# Atmega32_Breakout.net
KiCad netlist of a schematic drawn in EAGLE
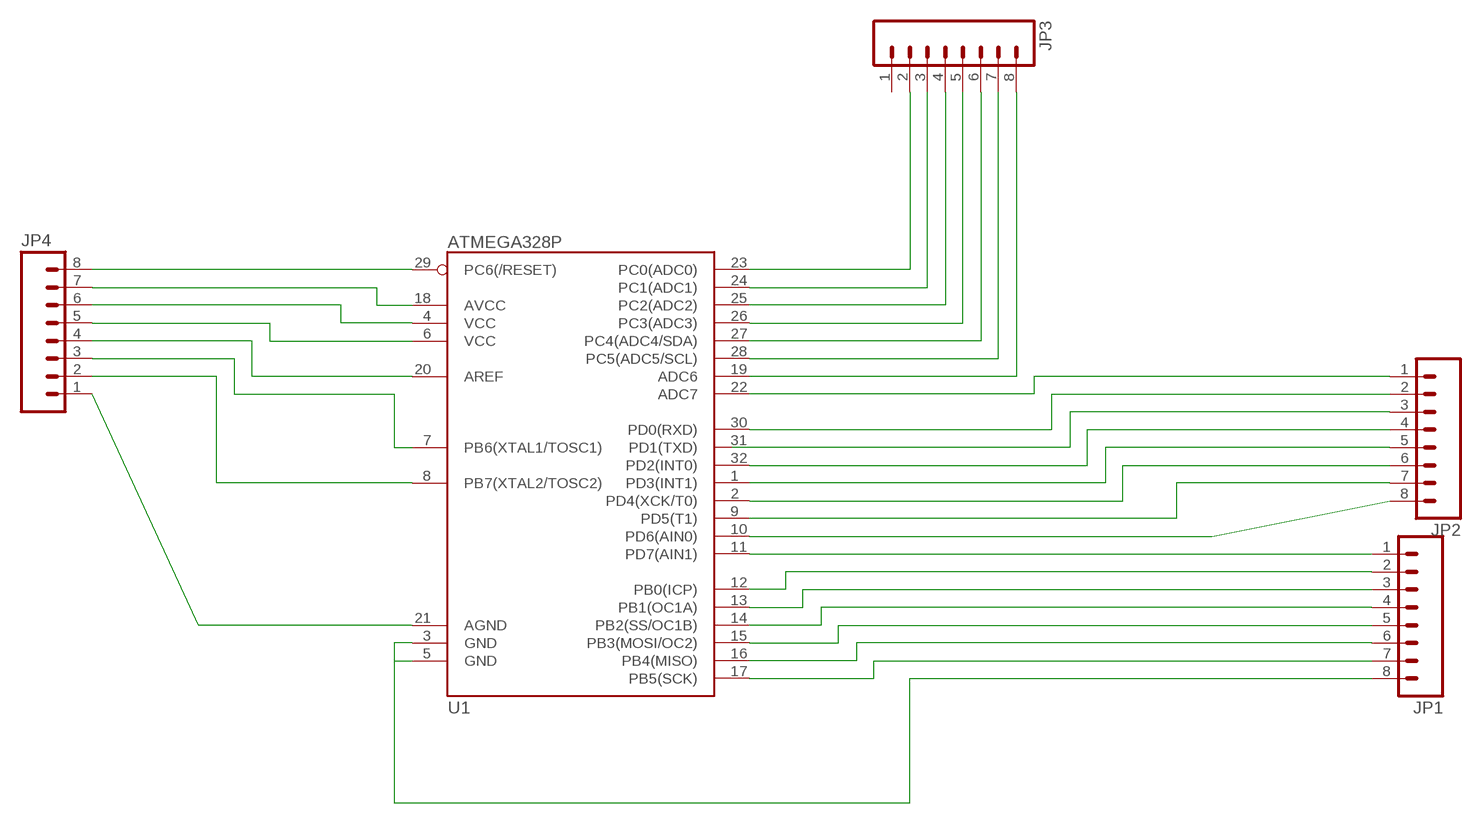
[diagram p0: schematic, sheet 1]

(export (version "E")
  (design (tool "Eeschema 10.0.6"))
  (components
    (comp (ref "JP1")
      (value "M08")
      (footprint "eagle-import:1X08_PIN1_NO_SILK")
      (libsource (lib "eagle-import") (part "M08"))
    )
    (comp (ref "JP2")
      (value "M08")
      (footprint "eagle-import:1X08_PIN1_NO_SILK")
      (libsource (lib "eagle-import") (part "M08"))
    )
    (comp (ref "JP3")
      (value "M08")
      (footprint "eagle-import:1X08_PIN1_NO_SILK")
      (libsource (lib "eagle-import") (part "M08"))
    )
    (comp (ref "JP4")
      (value "M08")
      (footprint "eagle-import:1X08_PIN1_NO_SILK")
      (libsource (lib "eagle-import") (part "M08"))
    )
    (comp (ref "U1")
      (value "ATMEGA328P")
      (footprint "eagle-import:TQFP32-08")
      (libsource (lib "eagle-import") (part "ATMEGA328_SMT"))
    )
  )
  (nets
    (net (code "1") (name "/VCC") (class "Default")
      (node (ref "JP4") (pin "5") (pinfunction "5_5") (pintype "passive"))
      (node (ref "JP4") (pin "6") (pinfunction "6_6") (pintype "passive"))
      (node (ref "U1") (pin "4") (pinfunction "VCC_4") (pintype "bidirectional"))
      (node (ref "U1") (pin "6") (pinfunction "VCC_6") (pintype "bidirectional"))
    )
    (net (code "2") (name "Net-(JP1-Pad8)") (class "Default")
      (node (ref "JP1") (pin "8") (pinfunction "8_8") (pintype "passive"))
      (node (ref "U1") (pin "3") (pinfunction "GND_3") (pintype "bidirectional"))
      (node (ref "U1") (pin "5") (pinfunction "GND_5") (pintype "bidirectional"))
    )
    (net (code "3") (name "Net-(U1-ADC6)") (class "Default")
      (node (ref "JP3") (pin "8") (pinfunction "8_8") (pintype "passive"))
      (node (ref "U1") (pin "19") (pinfunction "ADC6_19") (pintype "bidirectional"))
    )
    (net (code "4") (name "Net-(U1-ADC7)") (class "Default")
      (node (ref "JP2") (pin "1") (pinfunction "1_1") (pintype "passive"))
      (node (ref "U1") (pin "22") (pinfunction "ADC7_22") (pintype "bidirectional"))
    )
    (net (code "5") (name "Net-(U1-AGND)") (class "Default")
      (node (ref "JP4") (pin "1") (pinfunction "1_1") (pintype "passive"))
      (node (ref "U1") (pin "21") (pinfunction "AGND_21") (pintype "bidirectional"))
    )
    (net (code "6") (name "Net-(U1-AREF)") (class "Default")
      (node (ref "JP4") (pin "4") (pinfunction "4_4") (pintype "passive"))
      (node (ref "U1") (pin "20") (pinfunction "AREF_20") (pintype "bidirectional"))
    )
    (net (code "7") (name "Net-(U1-AVCC)") (class "Default")
      (node (ref "JP4") (pin "7") (pinfunction "7_7") (pintype "passive"))
      (node (ref "U1") (pin "18") (pinfunction "AVCC_18") (pintype "bidirectional"))
    )
    (net (code "8") (name "Net-(U1-PB0(ICP))") (class "Default")
      (node (ref "JP1") (pin "2") (pinfunction "2_2") (pintype "passive"))
      (node (ref "U1") (pin "12") (pinfunction "PB0(ICP)_12") (pintype "bidirectional"))
    )
    (net (code "9") (name "Net-(U1-PB1(OC1A))") (class "Default")
      (node (ref "JP1") (pin "3") (pinfunction "3_3") (pintype "passive"))
      (node (ref "U1") (pin "13") (pinfunction "PB1(OC1A)_13") (pintype "bidirectional"))
    )
    (net (code "10") (name "Net-(U1-PB2(SS{slash}OC1B))") (class "Default")
      (node (ref "JP1") (pin "4") (pinfunction "4_4") (pintype "passive"))
      (node (ref "U1") (pin "14") (pinfunction "PB2(SS/OC1B)_14") (pintype "bidirectional"))
    )
    (net (code "11") (name "Net-(U1-PB3(MOSI{slash}OC2))") (class "Default")
      (node (ref "JP1") (pin "5") (pinfunction "5_5") (pintype "passive"))
      (node (ref "U1") (pin "15") (pinfunction "PB3(MOSI/OC2)_15") (pintype "bidirectional"))
    )
    (net (code "12") (name "Net-(U1-PB4(MISO))") (class "Default")
      (node (ref "JP1") (pin "6") (pinfunction "6_6") (pintype "passive"))
      (node (ref "U1") (pin "16") (pinfunction "PB4(MISO)_16") (pintype "bidirectional"))
    )
    (net (code "13") (name "Net-(U1-PB5(SCK))") (class "Default")
      (node (ref "JP1") (pin "7") (pinfunction "7_7") (pintype "passive"))
      (node (ref "U1") (pin "17") (pinfunction "PB5(SCK)_17") (pintype "bidirectional"))
    )
    (net (code "14") (name "Net-(U1-PB6(XTAL1{slash}TOSC1))") (class "Default")
      (node (ref "JP4") (pin "3") (pinfunction "3_3") (pintype "passive"))
      (node (ref "U1") (pin "7") (pinfunction "PB6(XTAL1/TOSC1)_7") (pintype "bidirectional"))
    )
    (net (code "15") (name "Net-(U1-PB7(XTAL2{slash}TOSC2))") (class "Default")
      (node (ref "JP4") (pin "2") (pinfunction "2_2") (pintype "passive"))
      (node (ref "U1") (pin "8") (pinfunction "PB7(XTAL2/TOSC2)_8") (pintype "bidirectional"))
    )
    (net (code "16") (name "Net-(U1-PC0(ADC0))") (class "Default")
      (node (ref "JP3") (pin "2") (pinfunction "2_2") (pintype "passive"))
      (node (ref "U1") (pin "23") (pinfunction "PC0(ADC0)_23") (pintype "bidirectional"))
    )
    (net (code "17") (name "Net-(U1-PC1(ADC1))") (class "Default")
      (node (ref "JP3") (pin "3") (pinfunction "3_3") (pintype "passive"))
      (node (ref "U1") (pin "24") (pinfunction "PC1(ADC1)_24") (pintype "bidirectional"))
    )
    (net (code "18") (name "Net-(U1-PC2(ADC2))") (class "Default")
      (node (ref "JP3") (pin "4") (pinfunction "4_4") (pintype "passive"))
      (node (ref "U1") (pin "25") (pinfunction "PC2(ADC2)_25") (pintype "bidirectional"))
    )
    (net (code "19") (name "Net-(U1-PC3(ADC3))") (class "Default")
      (node (ref "JP3") (pin "5") (pinfunction "5_5") (pintype "passive"))
      (node (ref "U1") (pin "26") (pinfunction "PC3(ADC3)_26") (pintype "bidirectional"))
    )
    (net (code "20") (name "Net-(U1-PC4(ADC4{slash}SDA))") (class "Default")
      (node (ref "JP3") (pin "6") (pinfunction "6_6") (pintype "passive"))
      (node (ref "U1") (pin "27") (pinfunction "PC4(ADC4/SDA)_27") (pintype "bidirectional"))
    )
    (net (code "21") (name "Net-(U1-PC5(ADC5{slash}SCL))") (class "Default")
      (node (ref "JP3") (pin "7") (pinfunction "7_7") (pintype "passive"))
      (node (ref "U1") (pin "28") (pinfunction "PC5(ADC5/SCL)_28") (pintype "bidirectional"))
    )
    (net (code "22") (name "Net-(U1-PC6({slash}RESET))") (class "Default")
      (node (ref "JP4") (pin "8") (pinfunction "8_8") (pintype "passive"))
      (node (ref "U1") (pin "29") (pinfunction "PC6(/RESET)_29") (pintype "bidirectional"))
    )
    (net (code "23") (name "Net-(U1-PD0(RXD))") (class "Default")
      (node (ref "JP2") (pin "2") (pinfunction "2_2") (pintype "passive"))
      (node (ref "U1") (pin "30") (pinfunction "PD0(RXD)_30") (pintype "bidirectional"))
    )
    (net (code "24") (name "Net-(U1-PD2(INT0))") (class "Default")
      (node (ref "JP2") (pin "4") (pinfunction "4_4") (pintype "passive"))
      (node (ref "U1") (pin "32") (pinfunction "PD2(INT0)_32") (pintype "bidirectional"))
    )
    (net (code "25") (name "Net-(U1-PD3(INT1))") (class "Default")
      (node (ref "JP2") (pin "5") (pinfunction "5_5") (pintype "passive"))
      (node (ref "U1") (pin "1") (pinfunction "PD3(INT1)_1") (pintype "bidirectional"))
    )
    (net (code "26") (name "Net-(U1-PD4(XCK{slash}T0))") (class "Default")
      (node (ref "JP2") (pin "6") (pinfunction "6_6") (pintype "passive"))
      (node (ref "U1") (pin "2") (pinfunction "PD4(XCK/T0)_2") (pintype "bidirectional"))
    )
    (net (code "27") (name "Net-(U1-PD5(T1))") (class "Default")
      (node (ref "JP2") (pin "7") (pinfunction "7_7") (pintype "passive"))
      (node (ref "U1") (pin "9") (pinfunction "PD5(T1)_9") (pintype "bidirectional"))
    )
    (net (code "28") (name "Net-(U1-PD6(AIN0))") (class "Default")
      (node (ref "JP2") (pin "8") (pinfunction "8_8") (pintype "passive"))
      (node (ref "U1") (pin "10") (pinfunction "PD6(AIN0)_10") (pintype "bidirectional"))
    )
    (net (code "29") (name "Net-(U1-PD7(AIN1))") (class "Default")
      (node (ref "JP1") (pin "1") (pinfunction "1_1") (pintype "passive"))
      (node (ref "U1") (pin "11") (pinfunction "PD7(AIN1)_11") (pintype "bidirectional"))
    )
    (net (code "30") (name "unconnected-(JP2-Pad3)") (class "Default")
      (node (ref "JP2") (pin "3") (pinfunction "3_3") (pintype "passive"))
    )
    (net (code "31") (name "unconnected-(JP3-Pad1)") (class "Default")
      (node (ref "JP3") (pin "1") (pinfunction "1_1") (pintype "passive"))
    )
    (net (code "32") (name "unconnected-(U1-PD1(TXD)-Pad31)") (class "Default")
      (node (ref "U1") (pin "31") (pinfunction "PD1(TXD)_31") (pintype "bidirectional"))
    )
  )
)
